# Test_SEAx.net
KiCad netlist of a schematic drawn in Altium Designer
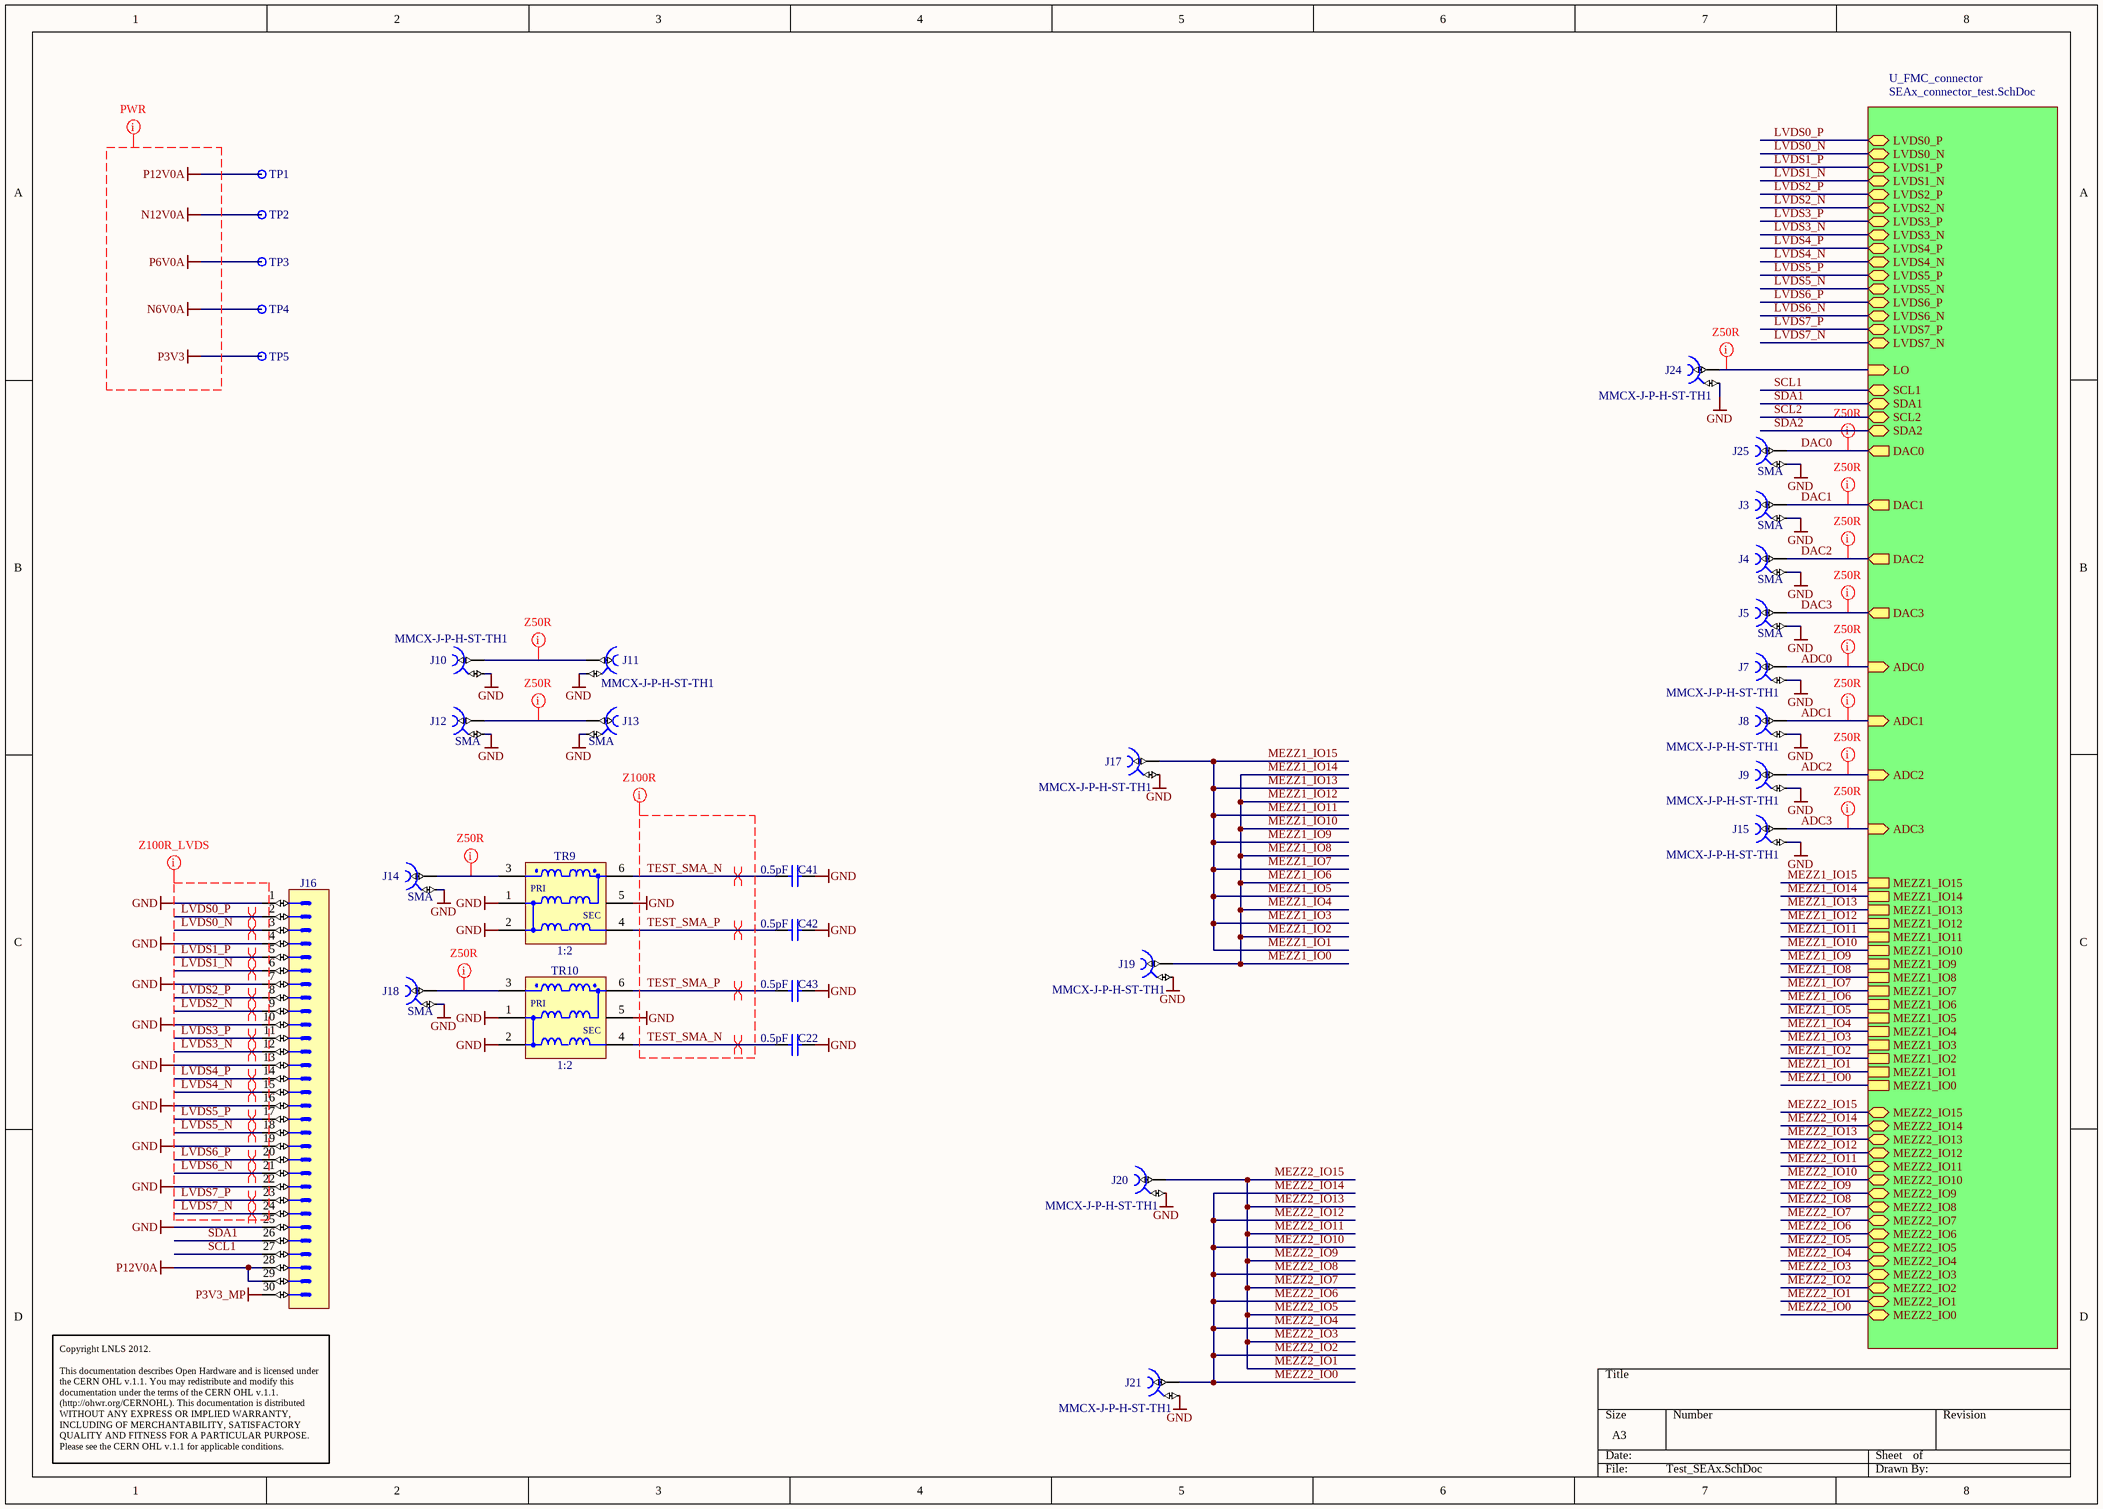
[diagram p0: Test_SEAx.SchDoc]

(export (version "E")
  (design (tool "Eeschema 10.0.6"))
  (components
    (comp (ref "C22")
      (value "0.5pF")
      (footprint "CAPC1005X50N")
      (description "Non-polarised capacitor")
      (fields
        (field (name "PART NUMBER") "CC0402_0.5PF_25V_0.05PF_AVX_04023J0R5ABSTR")
        (field (name "VOLTAGE") "25V")
        (field (name "AUTHOR") "CERN DEM JLC")
      )
      (libsource (lib "Capacitors") (part "Capacitor - non polarized"))
    )
    (comp (ref "C41")
      (value "0.5pF")
      (footprint "CAPC1005X50N")
      (description "Non-polarised capacitor")
      (fields
        (field (name "PART NUMBER") "CC0402_0.5PF_25V_0.05PF_AVX_04023J0R5ABSTR")
        (field (name "VOLTAGE") "25V")
        (field (name "AUTHOR") "CERN DEM JLC")
      )
      (libsource (lib "Capacitors") (part "Capacitor - non polarized"))
    )
    (comp (ref "C42")
      (value "0.5pF")
      (footprint "CAPC1005X50N")
      (description "Non-polarised capacitor")
      (fields
        (field (name "PART NUMBER") "CC0402_0.5PF_25V_0.05PF_AVX_04023J0R5ABSTR")
        (field (name "VOLTAGE") "25V")
        (field (name "AUTHOR") "CERN DEM JLC")
      )
      (libsource (lib "Capacitors") (part "Capacitor - non polarized"))
    )
    (comp (ref "C43")
      (value "0.5pF")
      (footprint "CAPC1005X50N")
      (description "Non-polarised capacitor")
      (fields
        (field (name "PART NUMBER") "CC0402_0.5PF_25V_0.05PF_AVX_04023J0R5ABSTR")
        (field (name "VOLTAGE") "25V")
        (field (name "AUTHOR") "CERN DEM JLC")
      )
      (libsource (lib "Capacitors") (part "Capacitor - non polarized"))
    )
    (comp (ref "J3")
      (value "SMA")
      (footprint "TYCO_5-1814832-1")
      (fields
        (field (name "PART NUMBER") "TYCO_5-1814832-1")
        (field (name "MANUFACTURER") "TYCO ELECTRONICS")
        (field (name "MANUFACTURER PART NUMBER") "5-1814832-1")
        (field (name "AUTHOR") "CERN DEM JLC")
      )
      (libsource (lib "Connectors") (part "Coax_1Female_1Shield"))
    )
    (comp (ref "J4")
      (value "SMA")
      (footprint "TYCO_5-1814832-1")
      (fields
        (field (name "PART NUMBER") "TYCO_5-1814832-1")
        (field (name "MANUFACTURER") "TYCO ELECTRONICS")
        (field (name "MANUFACTURER PART NUMBER") "5-1814832-1")
        (field (name "AUTHOR") "CERN DEM JLC")
      )
      (libsource (lib "Connectors") (part "Coax_1Female_1Shield"))
    )
    (comp (ref "J5")
      (value "SMA")
      (footprint "TYCO_5-1814832-1")
      (fields
        (field (name "PART NUMBER") "TYCO_5-1814832-1")
        (field (name "MANUFACTURER") "TYCO ELECTRONICS")
        (field (name "MANUFACTURER PART NUMBER") "5-1814832-1")
        (field (name "AUTHOR") "CERN DEM JLC")
      )
      (libsource (lib "Connectors") (part "Coax_1Female_1Shield"))
    )
    (comp (ref "J7")
      (value "Coax_1Female_1Shield")
      (footprint "SAMTEC_MMCX-J-P-H-ST-TH1")
      (fields
        (field (name "PART NUMBER") "SAMTEC_MMCX-J-P-H-ST-TH1")
        (field (name "MANUFACTURER") "SAMTEC")
        (field (name "MANUFACTURER PART NUMBER") "MMCX-J-P-H-ST-TH1")
        (field (name "AUTHOR") "CERN DEM JLC")
      )
      (libsource (lib "Connectors") (part "Coax_1Female_1Shield"))
    )
    (comp (ref "J8")
      (value "Coax_1Female_1Shield")
      (footprint "SAMTEC_MMCX-J-P-H-ST-TH1")
      (fields
        (field (name "PART NUMBER") "SAMTEC_MMCX-J-P-H-ST-TH1")
        (field (name "MANUFACTURER") "SAMTEC")
        (field (name "MANUFACTURER PART NUMBER") "MMCX-J-P-H-ST-TH1")
        (field (name "AUTHOR") "CERN DEM JLC")
      )
      (libsource (lib "Connectors") (part "Coax_1Female_1Shield"))
    )
    (comp (ref "J9")
      (value "Coax_1Female_1Shield")
      (footprint "SAMTEC_MMCX-J-P-H-ST-TH1")
      (fields
        (field (name "PART NUMBER") "SAMTEC_MMCX-J-P-H-ST-TH1")
        (field (name "MANUFACTURER") "SAMTEC")
        (field (name "MANUFACTURER PART NUMBER") "MMCX-J-P-H-ST-TH1")
        (field (name "AUTHOR") "CERN DEM JLC")
      )
      (libsource (lib "Connectors") (part "Coax_1Female_1Shield"))
    )
    (comp (ref "J10")
      (value "Coax_1Female_1Shield")
      (footprint "SAMTEC_MMCX-J-P-H-ST-TH1")
      (fields
        (field (name "PART NUMBER") "SAMTEC_MMCX-J-P-H-ST-TH1")
        (field (name "MANUFACTURER") "SAMTEC")
        (field (name "MANUFACTURER PART NUMBER") "MMCX-J-P-H-ST-TH1")
        (field (name "AUTHOR") "CERN DEM JLC")
      )
      (libsource (lib "Connectors") (part "Coax_1Female_1Shield"))
    )
    (comp (ref "J11")
      (value "Coax_1Female_1Shield")
      (footprint "SAMTEC_MMCX-J-P-H-ST-TH1")
      (fields
        (field (name "PART NUMBER") "SAMTEC_MMCX-J-P-H-ST-TH1")
        (field (name "MANUFACTURER") "SAMTEC")
        (field (name "MANUFACTURER PART NUMBER") "MMCX-J-P-H-ST-TH1")
        (field (name "AUTHOR") "CERN DEM JLC")
      )
      (libsource (lib "") (part "Coax_1Female_1Shield_1"))
    )
    (comp (ref "J12")
      (value "SMA")
      (footprint "TYCO_5-1814832-1")
      (fields
        (field (name "PART NUMBER") "TYCO_5-1814832-1")
        (field (name "MANUFACTURER") "TYCO ELECTRONICS")
        (field (name "MANUFACTURER PART NUMBER") "5-1814832-1")
        (field (name "AUTHOR") "CERN DEM JLC")
      )
      (libsource (lib "Connectors") (part "Coax_1Female_1Shield"))
    )
    (comp (ref "J13")
      (value "SMA")
      (footprint "TYCO_5-1814832-1")
      (fields
        (field (name "PART NUMBER") "TYCO_5-1814832-1")
        (field (name "MANUFACTURER") "TYCO ELECTRONICS")
        (field (name "MANUFACTURER PART NUMBER") "5-1814832-1")
        (field (name "AUTHOR") "CERN DEM JLC")
      )
      (libsource (lib "") (part "Coax_1Female_1Shield_1"))
    )
    (comp (ref "J14")
      (value "SMA")
      (footprint "TYCO_5-1814832-1")
      (fields
        (field (name "PART NUMBER") "TYCO_5-1814832-1")
        (field (name "MANUFACTURER") "TYCO ELECTRONICS")
        (field (name "MANUFACTURER PART NUMBER") "5-1814832-1")
        (field (name "AUTHOR") "CERN DEM JLC")
      )
      (libsource (lib "Connectors") (part "Coax_1Female_1Shield"))
    )
    (comp (ref "J15")
      (value "Coax_1Female_1Shield")
      (footprint "SAMTEC_MMCX-J-P-H-ST-TH1")
      (fields
        (field (name "PART NUMBER") "SAMTEC_MMCX-J-P-H-ST-TH1")
        (field (name "MANUFACTURER") "SAMTEC")
        (field (name "MANUFACTURER PART NUMBER") "MMCX-J-P-H-ST-TH1")
        (field (name "AUTHOR") "CERN DEM JLC")
      )
      (libsource (lib "Connectors") (part "Coax_1Female_1Shield"))
    )
    (comp (ref "J16")
      (value "~")
      (footprint "3M_N2530-6002RB")
      (description "Connector 30 Male")
      (fields
        (field (name "PART NUMBER") "3M_N2530-6002RB")
        (field (name "MANUFACTURER") "3M")
        (field (name "AUTHOR") "CERN DEM JLC")
      )
      (libsource (lib "Connectors") (part "Connector 30 Male"))
    )
    (comp (ref "J17")
      (value "Coax_1Female_1Shield")
      (footprint "SAMTEC_MMCX-J-P-H-ST-TH1")
      (fields
        (field (name "PART NUMBER") "SAMTEC_MMCX-J-P-H-ST-TH1")
        (field (name "MANUFACTURER") "SAMTEC")
        (field (name "MANUFACTURER PART NUMBER") "MMCX-J-P-H-ST-TH1")
        (field (name "AUTHOR") "CERN DEM JLC")
      )
      (libsource (lib "Connectors") (part "Coax_1Female_1Shield"))
    )
    (comp (ref "J18")
      (value "SMA")
      (footprint "TYCO_5-1814832-1")
      (fields
        (field (name "PART NUMBER") "TYCO_5-1814832-1")
        (field (name "MANUFACTURER") "TYCO ELECTRONICS")
        (field (name "MANUFACTURER PART NUMBER") "5-1814832-1")
        (field (name "AUTHOR") "CERN DEM JLC")
      )
      (libsource (lib "Connectors") (part "Coax_1Female_1Shield"))
    )
    (comp (ref "J19")
      (value "Coax_1Female_1Shield")
      (footprint "SAMTEC_MMCX-J-P-H-ST-TH1")
      (fields
        (field (name "PART NUMBER") "SAMTEC_MMCX-J-P-H-ST-TH1")
        (field (name "MANUFACTURER") "SAMTEC")
        (field (name "MANUFACTURER PART NUMBER") "MMCX-J-P-H-ST-TH1")
        (field (name "AUTHOR") "CERN DEM JLC")
      )
      (libsource (lib "Connectors") (part "Coax_1Female_1Shield"))
    )
    (comp (ref "J20")
      (value "Coax_1Female_1Shield")
      (footprint "SAMTEC_MMCX-J-P-H-ST-TH1")
      (fields
        (field (name "PART NUMBER") "SAMTEC_MMCX-J-P-H-ST-TH1")
        (field (name "MANUFACTURER") "SAMTEC")
        (field (name "MANUFACTURER PART NUMBER") "MMCX-J-P-H-ST-TH1")
        (field (name "AUTHOR") "CERN DEM JLC")
      )
      (libsource (lib "Connectors") (part "Coax_1Female_1Shield"))
    )
    (comp (ref "J21")
      (value "Coax_1Female_1Shield")
      (footprint "SAMTEC_MMCX-J-P-H-ST-TH1")
      (fields
        (field (name "PART NUMBER") "SAMTEC_MMCX-J-P-H-ST-TH1")
        (field (name "MANUFACTURER") "SAMTEC")
        (field (name "MANUFACTURER PART NUMBER") "MMCX-J-P-H-ST-TH1")
        (field (name "AUTHOR") "CERN DEM JLC")
      )
      (libsource (lib "Connectors") (part "Coax_1Female_1Shield"))
    )
    (comp (ref "J24")
      (value "Coax_1Female_1Shield")
      (footprint "SAMTEC_MMCX-J-P-H-ST-TH1")
      (fields
        (field (name "PART NUMBER") "SAMTEC_MMCX-J-P-H-ST-TH1")
        (field (name "MANUFACTURER") "SAMTEC")
        (field (name "MANUFACTURER PART NUMBER") "MMCX-J-P-H-ST-TH1")
        (field (name "AUTHOR") "CERN DEM JLC")
      )
      (libsource (lib "Connectors") (part "Coax_1Female_1Shield"))
    )
    (comp (ref "J25")
      (value "SMA")
      (footprint "TYCO_5-1814832-1")
      (fields
        (field (name "PART NUMBER") "TYCO_5-1814832-1")
        (field (name "MANUFACTURER") "TYCO ELECTRONICS")
        (field (name "MANUFACTURER PART NUMBER") "5-1814832-1")
        (field (name "AUTHOR") "CERN DEM JLC")
      )
      (libsource (lib "Connectors") (part "Coax_1Female_1Shield"))
    )
    (comp (ref "TP1")
      (value "Test Point")
      (footprint "TPS127")
      (fields (field (name "PART NUMBER") "SMD_PAD_1.27X1.27MM") (field (name "AUTHOR") "CERN DEM JLC"))
      (libsource (lib "Eletro-mechanical") (part "Test Point"))
    )
    (comp (ref "TP2")
      (value "Test Point")
      (footprint "TPS127")
      (fields (field (name "PART NUMBER") "SMD_PAD_1.27X1.27MM") (field (name "AUTHOR") "CERN DEM JLC"))
      (libsource (lib "Eletro-mechanical") (part "Test Point"))
    )
    (comp (ref "TP3")
      (value "Test Point")
      (footprint "TPS127")
      (fields (field (name "PART NUMBER") "SMD_PAD_1.27X1.27MM") (field (name "AUTHOR") "CERN DEM JLC"))
      (libsource (lib "Eletro-mechanical") (part "Test Point"))
    )
    (comp (ref "TP4")
      (value "Test Point")
      (footprint "TPS127")
      (fields (field (name "PART NUMBER") "SMD_PAD_1.27X1.27MM") (field (name "AUTHOR") "CERN DEM JLC"))
      (libsource (lib "Eletro-mechanical") (part "Test Point"))
    )
    (comp (ref "TP5")
      (value "Test Point")
      (footprint "TPS127")
      (fields (field (name "PART NUMBER") "SMD_PAD_1.27X1.27MM") (field (name "AUTHOR") "CERN DEM JLC"))
      (libsource (lib "Eletro-mechanical") (part "Test Point"))
    )
    (comp (ref "TR9")
      (value "1:2")
      (footprint "XFMR_MINI-CIRCUITS_DB1627")
      (description "50 OHMS 10 to 4000 MHz RF Transformer")
      (fields
        (field (name "PART NUMBER") "XFMR_MINI-CIRCUITS_TCM2-43X+")
        (field (name "POWER") "0.4W")
        (field (name "AUTHOR") "CERN DEM BC")
      )
      (libsource (lib "Inductors & Transformers") (part "XFMR_MINI-CIRCUITS_TCM2-43X"))
    )
    (comp (ref "TR10")
      (value "1:2")
      (footprint "XFMR_MINI-CIRCUITS_DB1627")
      (description "50 OHMS 10 to 4000 MHz RF Transformer")
      (fields
        (field (name "PART NUMBER") "XFMR_MINI-CIRCUITS_TCM2-43X+")
        (field (name "POWER") "0.4W")
        (field (name "AUTHOR") "CERN DEM BC")
      )
      (libsource (lib "Inductors & Transformers") (part "XFMR_MINI-CIRCUITS_TCM2-43X"))
    )
  )
  (nets
    (net (code "1") (name "/ADC0") (class "Default")
      (node (ref "J7") (pin "1") (pinfunction "1_1") (pintype "bidirectional"))
    )
    (net (code "2") (name "/ADC1") (class "Default")
      (node (ref "J8") (pin "1") (pinfunction "1_1") (pintype "bidirectional"))
    )
    (net (code "3") (name "/ADC2") (class "Default")
      (node (ref "J9") (pin "1") (pinfunction "1_1") (pintype "bidirectional"))
    )
    (net (code "4") (name "/ADC3") (class "Default")
      (node (ref "J15") (pin "1") (pinfunction "1_1") (pintype "bidirectional"))
    )
    (net (code "5") (name "/DAC0") (class "Default")
      (node (ref "J25") (pin "1") (pinfunction "1_1") (pintype "bidirectional"))
    )
    (net (code "6") (name "/DAC1") (class "Default")
      (node (ref "J3") (pin "1") (pinfunction "1_1") (pintype "bidirectional"))
    )
    (net (code "7") (name "/DAC2") (class "Default")
      (node (ref "J4") (pin "1") (pinfunction "1_1") (pintype "bidirectional"))
    )
    (net (code "8") (name "/DAC3") (class "Default")
      (node (ref "J5") (pin "1") (pinfunction "1_1") (pintype "bidirectional"))
    )
    (net (code "9") (name "/LO") (class "Default")
      (node (ref "J24") (pin "1") (pinfunction "1_1") (pintype "bidirectional"))
    )
    (net (code "10") (name "/LVDS0_N") (class "Default")
      (node (ref "J16") (pin "3") (pinfunction "3_3") (pintype "bidirectional"))
    )
    (net (code "11") (name "/LVDS0_P") (class "Default")
      (node (ref "J16") (pin "2") (pinfunction "2_2") (pintype "bidirectional"))
    )
    (net (code "12") (name "/LVDS1_N") (class "Default")
      (node (ref "J16") (pin "6") (pinfunction "6_6") (pintype "bidirectional"))
    )
    (net (code "13") (name "/LVDS1_P") (class "Default")
      (node (ref "J16") (pin "5") (pinfunction "5_5") (pintype "bidirectional"))
    )
    (net (code "14") (name "/LVDS2_N") (class "Default")
      (node (ref "J16") (pin "9") (pinfunction "9_9") (pintype "bidirectional"))
    )
    (net (code "15") (name "/LVDS2_P") (class "Default")
      (node (ref "J16") (pin "8") (pinfunction "8_8") (pintype "bidirectional"))
    )
    (net (code "16") (name "/LVDS3_N") (class "Default")
      (node (ref "J16") (pin "12") (pinfunction "12_12") (pintype "bidirectional"))
    )
    (net (code "17") (name "/LVDS3_P") (class "Default")
      (node (ref "J16") (pin "11") (pinfunction "11_11") (pintype "bidirectional"))
    )
    (net (code "18") (name "/LVDS4_N") (class "Default")
      (node (ref "J16") (pin "15") (pinfunction "15_15") (pintype "bidirectional"))
    )
    (net (code "19") (name "/LVDS4_P") (class "Default")
      (node (ref "J16") (pin "14") (pinfunction "14_14") (pintype "bidirectional"))
    )
    (net (code "20") (name "/LVDS5_N") (class "Default")
      (node (ref "J16") (pin "18") (pinfunction "18_18") (pintype "bidirectional"))
    )
    (net (code "21") (name "/LVDS5_P") (class "Default")
      (node (ref "J16") (pin "17") (pinfunction "17_17") (pintype "bidirectional"))
    )
    (net (code "22") (name "/LVDS6_N") (class "Default")
      (node (ref "J16") (pin "21") (pinfunction "21_21") (pintype "bidirectional"))
    )
    (net (code "23") (name "/LVDS6_P") (class "Default")
      (node (ref "J16") (pin "20") (pinfunction "20_20") (pintype "bidirectional"))
    )
    (net (code "24") (name "/LVDS7_N") (class "Default")
      (node (ref "J16") (pin "24") (pinfunction "24_24") (pintype "bidirectional"))
    )
    (net (code "25") (name "/LVDS7_P") (class "Default")
      (node (ref "J16") (pin "23") (pinfunction "23_23") (pintype "bidirectional"))
    )
    (net (code "26") (name "/MEZZ1_IO0") (class "Default")
      (node (ref "J19") (pin "1") (pinfunction "1_1") (pintype "bidirectional"))
    )
    (net (code "27") (name "/MEZZ1_IO1") (class "Default")
      (node (ref "J17") (pin "1") (pinfunction "1_1") (pintype "bidirectional"))
    )
    (net (code "28") (name "/MEZZ2_IO0") (class "Default")
      (node (ref "J21") (pin "1") (pinfunction "1_1") (pintype "bidirectional"))
    )
    (net (code "29") (name "/MEZZ2_IO1") (class "Default")
      (node (ref "J20") (pin "1") (pinfunction "1_1") (pintype "bidirectional"))
    )
    (net (code "30") (name "/SCL1") (class "Default")
      (node (ref "J16") (pin "27") (pinfunction "27_27") (pintype "bidirectional"))
    )
    (net (code "32") (name "/SDA1") (class "Default")
      (node (ref "J16") (pin "26") (pinfunction "26_26") (pintype "bidirectional"))
    )
    (net (code "34") (name "/TEST_SMA_N") (class "Default")
      (node (ref "C22") (pin "1") (pinfunction "1_1") (pintype "passive"))
      (node (ref "C41") (pin "1") (pinfunction "1_1") (pintype "passive"))
      (node (ref "TR10") (pin "4") (pinfunction "S1_4") (pintype "passive"))
      (node (ref "TR9") (pin "6") (pinfunction "S1_6") (pintype "passive"))
    )
    (net (code "35") (name "/TEST_SMA_P") (class "Default")
      (node (ref "C42") (pin "1") (pinfunction "1_1") (pintype "passive"))
      (node (ref "C43") (pin "1") (pinfunction "1_1") (pintype "passive"))
      (node (ref "TR10") (pin "6") (pinfunction "S1_6") (pintype "passive"))
      (node (ref "TR9") (pin "4") (pinfunction "S1_4") (pintype "passive"))
    )
    (net (code "36") (name "GND") (class "Default")
      (node (ref "C22") (pin "2") (pinfunction "2_2") (pintype "passive"))
      (node (ref "C41") (pin "2") (pinfunction "2_2") (pintype "passive"))
      (node (ref "C42") (pin "2") (pinfunction "2_2") (pintype "passive"))
      (node (ref "C43") (pin "2") (pinfunction "2_2") (pintype "passive"))
      (node (ref "J10") (pin "2") (pinfunction "2_2") (pintype "bidirectional"))
      (node (ref "J11") (pin "2") (pinfunction "2_2") (pintype "bidirectional"))
      (node (ref "J12") (pin "2") (pinfunction "2_2") (pintype "bidirectional"))
      (node (ref "J13") (pin "2") (pinfunction "2_2") (pintype "bidirectional"))
      (node (ref "J14") (pin "2") (pinfunction "2_2") (pintype "bidirectional"))
      (node (ref "J15") (pin "2") (pinfunction "2_2") (pintype "bidirectional"))
      (node (ref "J16") (pin "1") (pinfunction "1_1") (pintype "bidirectional"))
      (node (ref "J16") (pin "10") (pinfunction "10_10") (pintype "bidirectional"))
      (node (ref "J16") (pin "13") (pinfunction "13_13") (pintype "bidirectional"))
      (node (ref "J16") (pin "16") (pinfunction "16_16") (pintype "bidirectional"))
      (node (ref "J16") (pin "19") (pinfunction "19_19") (pintype "bidirectional"))
      (node (ref "J16") (pin "22") (pinfunction "22_22") (pintype "bidirectional"))
      (node (ref "J16") (pin "25") (pinfunction "25_25") (pintype "bidirectional"))
      (node (ref "J16") (pin "4") (pinfunction "4_4") (pintype "bidirectional"))
      (node (ref "J16") (pin "7") (pinfunction "7_7") (pintype "bidirectional"))
      (node (ref "J17") (pin "2") (pinfunction "2_2") (pintype "bidirectional"))
      (node (ref "J18") (pin "2") (pinfunction "2_2") (pintype "bidirectional"))
      (node (ref "J19") (pin "2") (pinfunction "2_2") (pintype "bidirectional"))
      (node (ref "J20") (pin "2") (pinfunction "2_2") (pintype "bidirectional"))
      (node (ref "J21") (pin "2") (pinfunction "2_2") (pintype "bidirectional"))
      (node (ref "J24") (pin "2") (pinfunction "2_2") (pintype "bidirectional"))
      (node (ref "J25") (pin "2") (pinfunction "2_2") (pintype "bidirectional"))
      (node (ref "J3") (pin "2") (pinfunction "2_2") (pintype "bidirectional"))
      (node (ref "J4") (pin "2") (pinfunction "2_2") (pintype "bidirectional"))
      (node (ref "J5") (pin "2") (pinfunction "2_2") (pintype "bidirectional"))
      (node (ref "J7") (pin "2") (pinfunction "2_2") (pintype "bidirectional"))
      (node (ref "J8") (pin "2") (pinfunction "2_2") (pintype "bidirectional"))
      (node (ref "J9") (pin "2") (pinfunction "2_2") (pintype "bidirectional"))
      (node (ref "TR10") (pin "1") (pinfunction "P1_1") (pintype "passive"))
      (node (ref "TR10") (pin "2") (pinfunction "P1_2") (pintype "passive"))
      (node (ref "TR10") (pin "5") (pinfunction "NC_5") (pintype "passive"))
      (node (ref "TR9") (pin "1") (pinfunction "P1_1") (pintype "passive"))
      (node (ref "TR9") (pin "2") (pinfunction "P1_2") (pintype "passive"))
      (node (ref "TR9") (pin "5") (pinfunction "NC_5") (pintype "passive"))
    )
    (net (code "37") (name "N6V0A") (class "Default")
      (node (ref "TP4") (pin "1") (pinfunction "1_1") (pintype "bidirectional"))
    )
    (net (code "38") (name "N12V0A") (class "Default")
      (node (ref "TP2") (pin "1") (pinfunction "1_1") (pintype "bidirectional"))
    )
    (net (code "39") (name "Net-(J10-Pad1)") (class "Default")
      (node (ref "J10") (pin "1") (pinfunction "1_1") (pintype "bidirectional"))
      (node (ref "J11") (pin "1") (pinfunction "1_1") (pintype "bidirectional"))
    )
    (net (code "40") (name "Net-(J12-Pad1)") (class "Default")
      (node (ref "J12") (pin "1") (pinfunction "1_1") (pintype "bidirectional"))
      (node (ref "J13") (pin "1") (pinfunction "1_1") (pintype "bidirectional"))
    )
    (net (code "41") (name "Net-(J14-Pad1)") (class "Default")
      (node (ref "J14") (pin "1") (pinfunction "1_1") (pintype "bidirectional"))
      (node (ref "TR9") (pin "3") (pinfunction "P1_3") (pintype "passive"))
    )
    (net (code "42") (name "Net-(J18-Pad1)") (class "Default")
      (node (ref "J18") (pin "1") (pinfunction "1_1") (pintype "bidirectional"))
      (node (ref "TR10") (pin "3") (pinfunction "P1_3") (pintype "passive"))
    )
    (net (code "43") (name "P3V3") (class "Default")
      (node (ref "TP5") (pin "1") (pinfunction "1_1") (pintype "bidirectional"))
    )
    (net (code "44") (name "P3V3_MP") (class "Default")
      (node (ref "J16") (pin "30") (pinfunction "30_30") (pintype "bidirectional"))
    )
    (net (code "45") (name "P6V0A") (class "Default")
      (node (ref "TP3") (pin "1") (pinfunction "1_1") (pintype "bidirectional"))
    )
    (net (code "46") (name "P12V0A") (class "Default")
      (node (ref "J16") (pin "28") (pinfunction "28_28") (pintype "bidirectional"))
      (node (ref "J16") (pin "29") (pinfunction "29_29") (pintype "bidirectional"))
      (node (ref "TP1") (pin "1") (pinfunction "1_1") (pintype "bidirectional"))
    )
  )
)
